# PMIC.net
KiCad netlist of a schematic drawn in Altium Designer
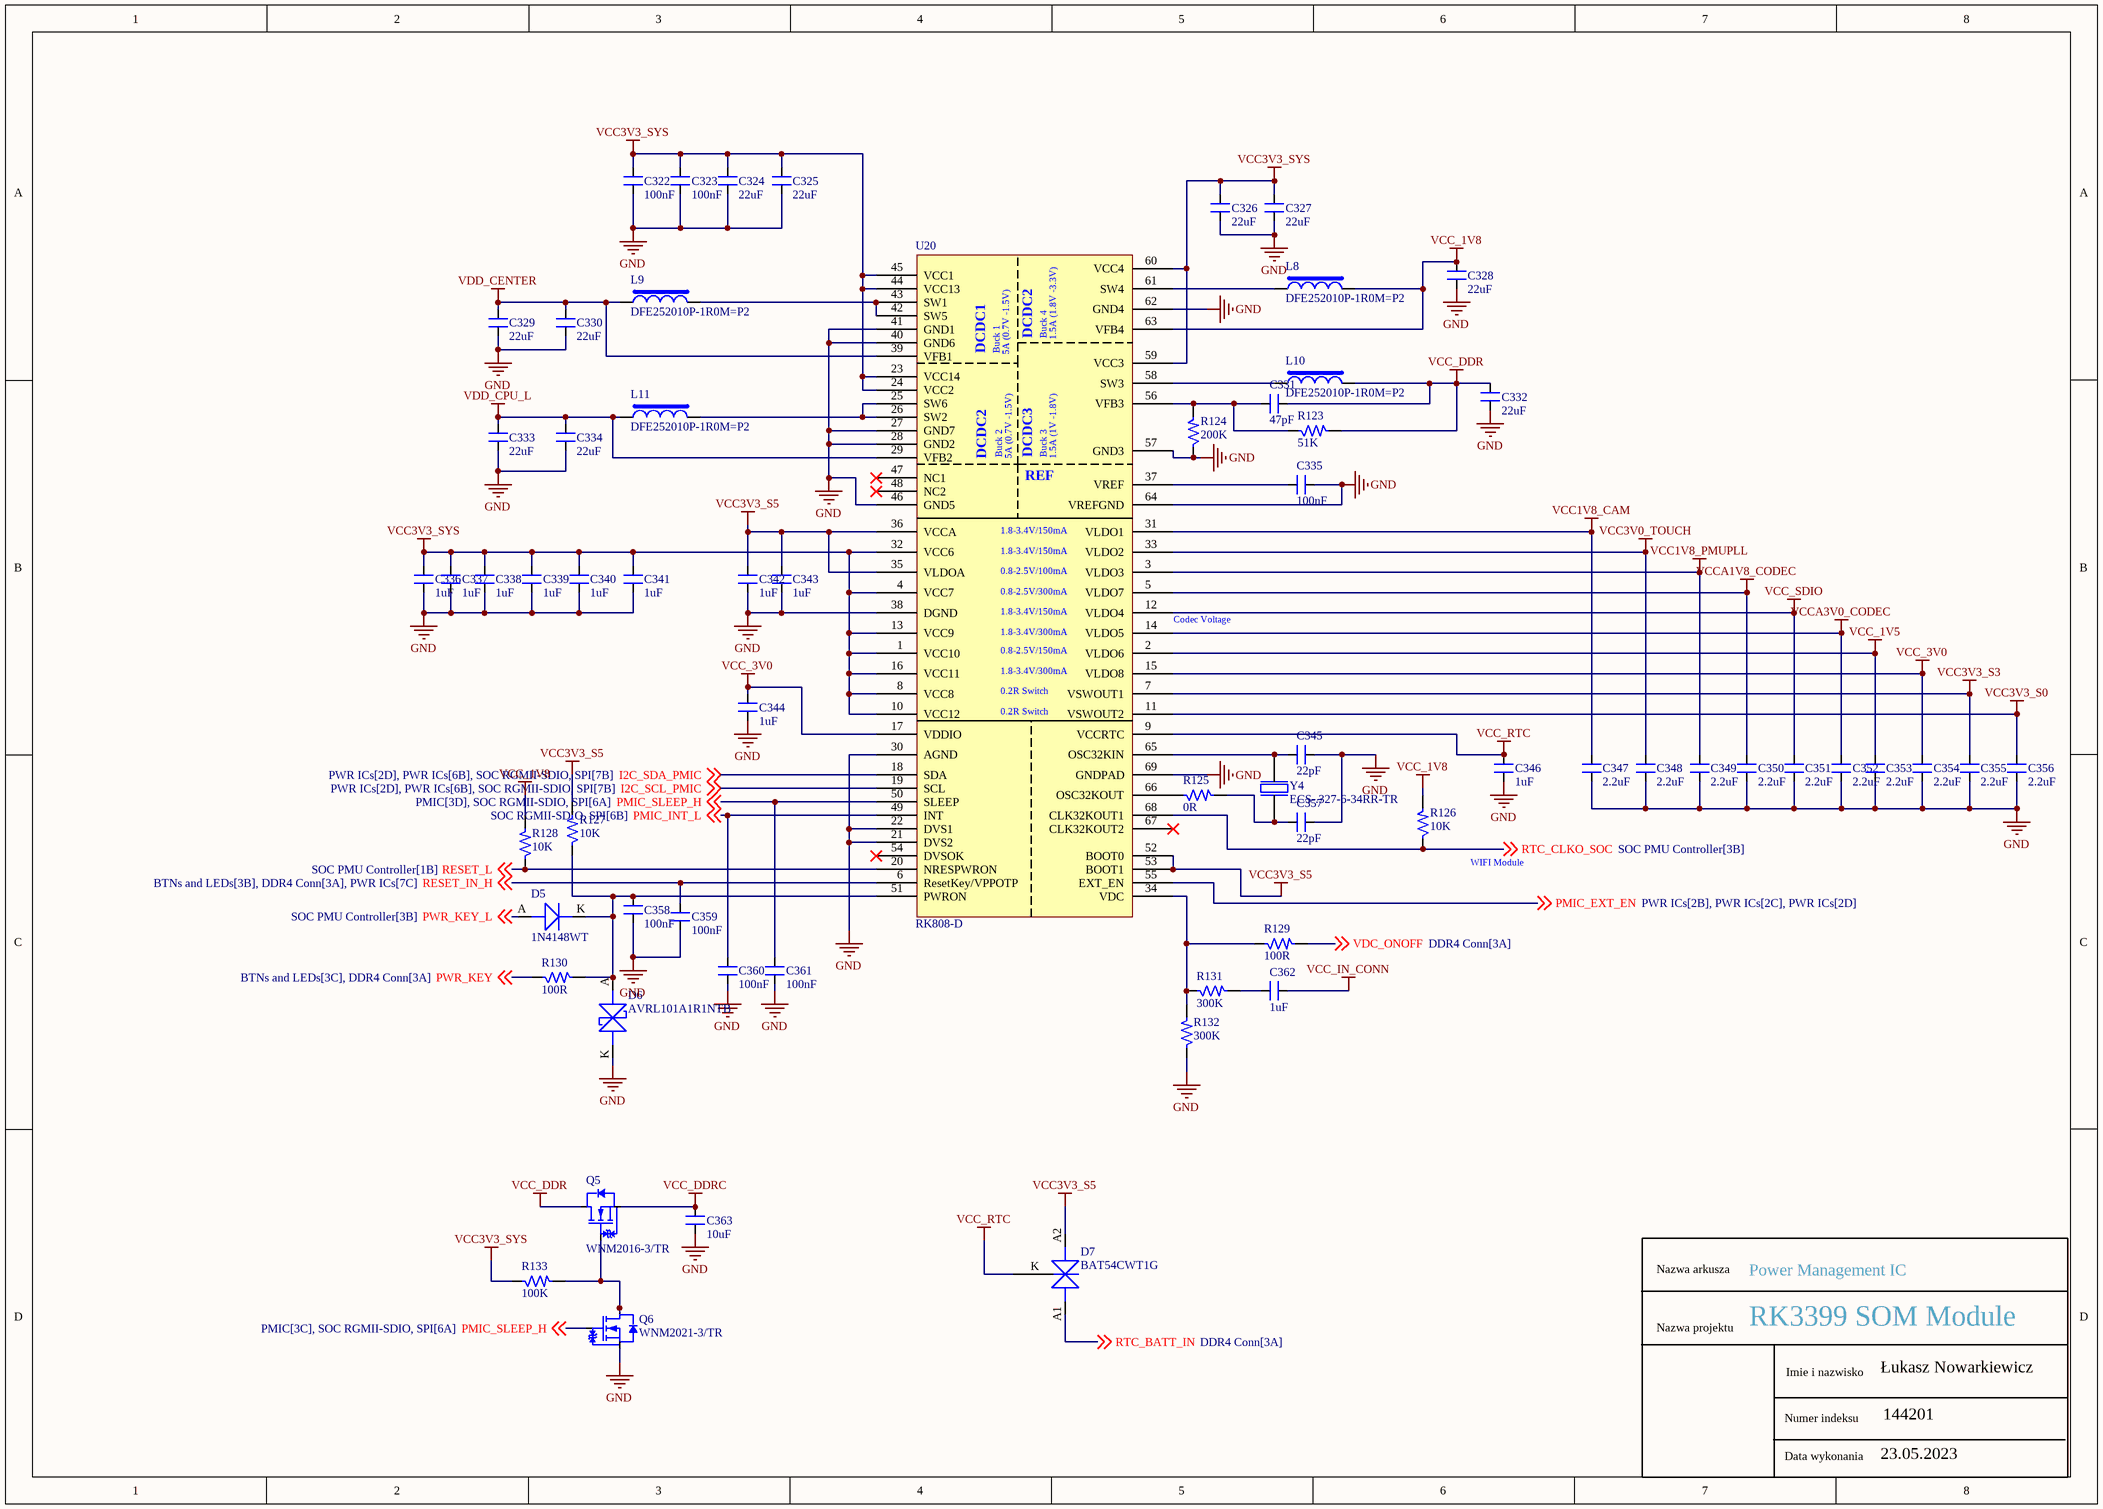
[diagram p0: PMIC.SchDoc]

(export (version "E")
  (design (tool "Eeschema 10.0.6"))
  (components
    (comp (ref "C322")
      (value "100nF")
      (footprint "CAP_0402")
      (description "0.1µF ±10% 25V Ceramic Capacitor X7R 0402 (1005 Metric)")
      (fields
        (field (name "MANUFACTURER") "Walsin Technology Corporation")
        (field (name "MANUFACTURER PART NUMBER") "0402B104K250CT")
      )
      (libsource (lib "RK3399 _Module_Schlib") (part "CAP_100nF-25V-10%-0402"))
    )
    (comp (ref "C323")
      (value "100nF")
      (footprint "CAP_0402")
      (description "0.1µF ±10% 25V Ceramic Capacitor X7R 0402 (1005 Metric)")
      (fields
        (field (name "MANUFACTURER") "Walsin Technology Corporation")
        (field (name "MANUFACTURER PART NUMBER") "0402B104K250CT")
      )
      (libsource (lib "RK3399 _Module_Schlib") (part "CAP_100nF-25V-10%-0402"))
    )
    (comp (ref "C324")
      (value "22uF")
      (footprint "CAP_0603")
      (description "22µF ±20% 10V Ceramic Capacitor X5R 0603 (1608 Metric)")
      (fields
        (field (name "MANUFACTURER") "Murata Electronics")
        (field (name "MANUFACTURER PART NUMBER") "GRM188R61A226ME15D")
      )
      (libsource (lib "RK3399 _Module_Schlib") (part "CAP_22uF-10V-20%-0603"))
    )
    (comp (ref "C325")
      (value "22uF")
      (footprint "CAP_0603")
      (description "22µF ±20% 10V Ceramic Capacitor X5R 0603 (1608 Metric)")
      (fields
        (field (name "MANUFACTURER") "Murata Electronics")
        (field (name "MANUFACTURER PART NUMBER") "GRM188R61A226ME15D")
      )
      (libsource (lib "RK3399 _Module_Schlib") (part "CAP_22uF-10V-20%-0603"))
    )
    (comp (ref "C326")
      (value "22uF")
      (footprint "CAP_0603")
      (description "22µF ±20% 10V Ceramic Capacitor X5R 0603 (1608 Metric)")
      (fields
        (field (name "MANUFACTURER") "Murata Electronics")
        (field (name "MANUFACTURER PART NUMBER") "GRM188R61A226ME15D")
      )
      (libsource (lib "RK3399 _Module_Schlib") (part "CAP_22uF-10V-20%-0603"))
    )
    (comp (ref "C327")
      (value "22uF")
      (footprint "CAP_0603")
      (description "22µF ±20% 10V Ceramic Capacitor X5R 0603 (1608 Metric)")
      (fields
        (field (name "MANUFACTURER") "Murata Electronics")
        (field (name "MANUFACTURER PART NUMBER") "GRM188R61A226ME15D")
      )
      (libsource (lib "RK3399 _Module_Schlib") (part "CAP_22uF-10V-20%-0603"))
    )
    (comp (ref "C328")
      (value "22uF")
      (footprint "CAP_0603")
      (description "22µF ±20% 10V Ceramic Capacitor X5R 0603 (1608 Metric)")
      (fields
        (field (name "MANUFACTURER") "Murata Electronics")
        (field (name "MANUFACTURER PART NUMBER") "GRM188R61A226ME15D")
      )
      (libsource (lib "RK3399 _Module_Schlib") (part "CAP_22uF-10V-20%-0603"))
    )
    (comp (ref "C329")
      (value "22uF")
      (footprint "CAP_0603")
      (description "22µF ±20% 10V Ceramic Capacitor X5R 0603 (1608 Metric)")
      (fields
        (field (name "MANUFACTURER") "Murata Electronics")
        (field (name "MANUFACTURER PART NUMBER") "GRM188R61A226ME15D")
      )
      (libsource (lib "RK3399 _Module_Schlib") (part "CAP_22uF-10V-20%-0603"))
    )
    (comp (ref "C330")
      (value "22uF")
      (footprint "CAP_0603")
      (description "22µF ±20% 10V Ceramic Capacitor X5R 0603 (1608 Metric)")
      (fields
        (field (name "MANUFACTURER") "Murata Electronics")
        (field (name "MANUFACTURER PART NUMBER") "GRM188R61A226ME15D")
      )
      (libsource (lib "RK3399 _Module_Schlib") (part "CAP_22uF-10V-20%-0603"))
    )
    (comp (ref "C331")
      (value "47pF")
      (footprint "CAP_0402")
      (description "47pF ±10% 10V Ceramic Capacitor C0G, NP0 0402 (1005 Metric)")
      (fields
        (field (name "MANUFACTURER") "KEMET")
        (field (name "MANUFACTURER PART NUMBER") "C0402C470K8GAC7867")
      )
      (libsource (lib "RK3399 _Module_Schlib") (part "CAP_47pF-10V-10%-0402"))
    )
    (comp (ref "C332")
      (value "22uF")
      (footprint "CAP_0603")
      (description "22µF ±20% 10V Ceramic Capacitor X5R 0603 (1608 Metric)")
      (fields
        (field (name "MANUFACTURER") "Murata Electronics")
        (field (name "MANUFACTURER PART NUMBER") "GRM188R61A226ME15D")
      )
      (libsource (lib "RK3399 _Module_Schlib") (part "CAP_22uF-10V-20%-0603"))
    )
    (comp (ref "C333")
      (value "22uF")
      (footprint "CAP_0603")
      (description "22µF ±20% 10V Ceramic Capacitor X5R 0603 (1608 Metric)")
      (fields
        (field (name "MANUFACTURER") "Murata Electronics")
        (field (name "MANUFACTURER PART NUMBER") "GRM188R61A226ME15D")
      )
      (libsource (lib "RK3399 _Module_Schlib") (part "CAP_22uF-10V-20%-0603"))
    )
    (comp (ref "C334")
      (value "22uF")
      (footprint "CAP_0603")
      (description "22µF ±20% 10V Ceramic Capacitor X5R 0603 (1608 Metric)")
      (fields
        (field (name "MANUFACTURER") "Murata Electronics")
        (field (name "MANUFACTURER PART NUMBER") "GRM188R61A226ME15D")
      )
      (libsource (lib "RK3399 _Module_Schlib") (part "CAP_22uF-10V-20%-0603"))
    )
    (comp (ref "C335")
      (value "100nF")
      (footprint "CAP_0402")
      (description "0.1µF ±10% 25V Ceramic Capacitor X7R 0402 (1005 Metric)")
      (fields
        (field (name "MANUFACTURER") "Walsin Technology Corporation")
        (field (name "MANUFACTURER PART NUMBER") "0402B104K250CT")
      )
      (libsource (lib "RK3399 _Module_Schlib") (part "CAP_100nF-25V-10%-0402"))
    )
    (comp (ref "C336")
      (value "1uF")
      (footprint "CAP_0402")
      (description "1µF ±10% 16V Ceramic Capacitor X5R 0402 (1005 Metric)")
      (fields
        (field (name "MANUFACTURER") "Knowles Novacap")
        (field (name "MANUFACTURER PART NUMBER") "0402BW105K160YT")
      )
      (libsource (lib "RK3399 _Module_Schlib") (part "CAP_1uF-16V-10%-0402"))
    )
    (comp (ref "C337")
      (value "1uF")
      (footprint "CAP_0402")
      (description "1µF ±10% 16V Ceramic Capacitor X5R 0402 (1005 Metric)")
      (fields
        (field (name "MANUFACTURER") "Knowles Novacap")
        (field (name "MANUFACTURER PART NUMBER") "0402BW105K160YT")
      )
      (libsource (lib "RK3399 _Module_Schlib") (part "CAP_1uF-16V-10%-0402"))
    )
    (comp (ref "C338")
      (value "1uF")
      (footprint "CAP_0402")
      (description "1µF ±10% 16V Ceramic Capacitor X5R 0402 (1005 Metric)")
      (fields
        (field (name "MANUFACTURER") "Knowles Novacap")
        (field (name "MANUFACTURER PART NUMBER") "0402BW105K160YT")
      )
      (libsource (lib "RK3399 _Module_Schlib") (part "CAP_1uF-16V-10%-0402"))
    )
    (comp (ref "C339")
      (value "1uF")
      (footprint "CAP_0402")
      (description "1µF ±10% 16V Ceramic Capacitor X5R 0402 (1005 Metric)")
      (fields
        (field (name "MANUFACTURER") "Knowles Novacap")
        (field (name "MANUFACTURER PART NUMBER") "0402BW105K160YT")
      )
      (libsource (lib "RK3399 _Module_Schlib") (part "CAP_1uF-16V-10%-0402"))
    )
    (comp (ref "C340")
      (value "1uF")
      (footprint "CAP_0402")
      (description "1µF ±10% 16V Ceramic Capacitor X5R 0402 (1005 Metric)")
      (fields
        (field (name "MANUFACTURER") "Knowles Novacap")
        (field (name "MANUFACTURER PART NUMBER") "0402BW105K160YT")
      )
      (libsource (lib "RK3399 _Module_Schlib") (part "CAP_1uF-16V-10%-0402"))
    )
    (comp (ref "C341")
      (value "1uF")
      (footprint "CAP_0402")
      (description "1µF ±10% 16V Ceramic Capacitor X5R 0402 (1005 Metric)")
      (fields
        (field (name "MANUFACTURER") "Knowles Novacap")
        (field (name "MANUFACTURER PART NUMBER") "0402BW105K160YT")
      )
      (libsource (lib "RK3399 _Module_Schlib") (part "CAP_1uF-16V-10%-0402"))
    )
    (comp (ref "C342")
      (value "1uF")
      (footprint "CAP_0402")
      (description "1µF ±10% 16V Ceramic Capacitor X5R 0402 (1005 Metric)")
      (fields
        (field (name "MANUFACTURER") "Knowles Novacap")
        (field (name "MANUFACTURER PART NUMBER") "0402BW105K160YT")
      )
      (libsource (lib "RK3399 _Module_Schlib") (part "CAP_1uF-16V-10%-0402"))
    )
    (comp (ref "C343")
      (value "1uF")
      (footprint "CAP_0402")
      (description "1µF ±10% 16V Ceramic Capacitor X5R 0402 (1005 Metric)")
      (fields
        (field (name "MANUFACTURER") "Knowles Novacap")
        (field (name "MANUFACTURER PART NUMBER") "0402BW105K160YT")
      )
      (libsource (lib "RK3399 _Module_Schlib") (part "CAP_1uF-16V-10%-0402"))
    )
    (comp (ref "C344")
      (value "1uF")
      (footprint "CAP_0402")
      (description "1µF ±10% 16V Ceramic Capacitor X5R 0402 (1005 Metric)")
      (fields
        (field (name "MANUFACTURER") "Knowles Novacap")
        (field (name "MANUFACTURER PART NUMBER") "0402BW105K160YT")
      )
      (libsource (lib "RK3399 _Module_Schlib") (part "CAP_1uF-16V-10%-0402"))
    )
    (comp (ref "C345")
      (value "22pF")
      (footprint "CAP_0402")
      (description "22pF ±10% 10V Ceramic Capacitor C0G, NP0 0402 (1005 Metric)")
      (fields
        (field (name "MANUFACTURER") "KEMET")
        (field (name "MANUFACTURER PART NUMBER") "C0402C220K8GACTU")
      )
      (libsource (lib "RK3399 _Module_Schlib") (part "CAP_22pF-10V-10%-0402"))
    )
    (comp (ref "C346")
      (value "1uF")
      (footprint "CAP_0402")
      (description "1µF ±10% 16V Ceramic Capacitor X5R 0402 (1005 Metric)")
      (fields
        (field (name "MANUFACTURER") "Knowles Novacap")
        (field (name "MANUFACTURER PART NUMBER") "0402BW105K160YT")
      )
      (libsource (lib "RK3399 _Module_Schlib") (part "CAP_1uF-16V-10%-0402"))
    )
    (comp (ref "C347")
      (value "2.2uF")
      (footprint "CAP_0402")
      (description "2.2µF ±10% 10V Ceramic Capacitor X5R 0402 (1005 Metric)")
      (fields
        (field (name "MANUFACTURER") "Murata Electronics")
        (field (name "MANUFACTURER PART NUMBER") "GRM155R61A225KE95D")
      )
      (libsource (lib "RK3399 _Module_Schlib") (part "CAP_2.2uF-10V-10%-0402"))
    )
    (comp (ref "C348")
      (value "2.2uF")
      (footprint "CAP_0402")
      (description "2.2µF ±10% 10V Ceramic Capacitor X5R 0402 (1005 Metric)")
      (fields
        (field (name "MANUFACTURER") "Murata Electronics")
        (field (name "MANUFACTURER PART NUMBER") "GRM155R61A225KE95D")
      )
      (libsource (lib "RK3399 _Module_Schlib") (part "CAP_2.2uF-10V-10%-0402"))
    )
    (comp (ref "C349")
      (value "2.2uF")
      (footprint "CAP_0402")
      (description "2.2µF ±10% 10V Ceramic Capacitor X5R 0402 (1005 Metric)")
      (fields
        (field (name "MANUFACTURER") "Murata Electronics")
        (field (name "MANUFACTURER PART NUMBER") "GRM155R61A225KE95D")
      )
      (libsource (lib "RK3399 _Module_Schlib") (part "CAP_2.2uF-10V-10%-0402"))
    )
    (comp (ref "C350")
      (value "2.2uF")
      (footprint "CAP_0402")
      (description "2.2µF ±10% 10V Ceramic Capacitor X5R 0402 (1005 Metric)")
      (fields
        (field (name "MANUFACTURER") "Murata Electronics")
        (field (name "MANUFACTURER PART NUMBER") "GRM155R61A225KE95D")
      )
      (libsource (lib "RK3399 _Module_Schlib") (part "CAP_2.2uF-10V-10%-0402"))
    )
    (comp (ref "C351")
      (value "2.2uF")
      (footprint "CAP_0402")
      (description "2.2µF ±10% 10V Ceramic Capacitor X5R 0402 (1005 Metric)")
      (fields
        (field (name "MANUFACTURER") "Murata Electronics")
        (field (name "MANUFACTURER PART NUMBER") "GRM155R61A225KE95D")
      )
      (libsource (lib "RK3399 _Module_Schlib") (part "CAP_2.2uF-10V-10%-0402"))
    )
    (comp (ref "C352")
      (value "2.2uF")
      (footprint "CAP_0402")
      (description "2.2µF ±10% 10V Ceramic Capacitor X5R 0402 (1005 Metric)")
      (fields
        (field (name "MANUFACTURER") "Murata Electronics")
        (field (name "MANUFACTURER PART NUMBER") "GRM155R61A225KE95D")
      )
      (libsource (lib "RK3399 _Module_Schlib") (part "CAP_2.2uF-10V-10%-0402"))
    )
    (comp (ref "C353")
      (value "2.2uF")
      (footprint "CAP_0402")
      (description "2.2µF ±10% 10V Ceramic Capacitor X5R 0402 (1005 Metric)")
      (fields
        (field (name "MANUFACTURER") "Murata Electronics")
        (field (name "MANUFACTURER PART NUMBER") "GRM155R61A225KE95D")
      )
      (libsource (lib "RK3399 _Module_Schlib") (part "CAP_2.2uF-10V-10%-0402"))
    )
    (comp (ref "C354")
      (value "2.2uF")
      (footprint "CAP_0402")
      (description "2.2µF ±10% 10V Ceramic Capacitor X5R 0402 (1005 Metric)")
      (fields
        (field (name "MANUFACTURER") "Murata Electronics")
        (field (name "MANUFACTURER PART NUMBER") "GRM155R61A225KE95D")
      )
      (libsource (lib "RK3399 _Module_Schlib") (part "CAP_2.2uF-10V-10%-0402"))
    )
    (comp (ref "C355")
      (value "2.2uF")
      (footprint "CAP_0402")
      (description "2.2µF ±10% 10V Ceramic Capacitor X5R 0402 (1005 Metric)")
      (fields
        (field (name "MANUFACTURER") "Murata Electronics")
        (field (name "MANUFACTURER PART NUMBER") "GRM155R61A225KE95D")
      )
      (libsource (lib "RK3399 _Module_Schlib") (part "CAP_2.2uF-10V-10%-0402"))
    )
    (comp (ref "C356")
      (value "2.2uF")
      (footprint "CAP_0402")
      (description "2.2µF ±10% 10V Ceramic Capacitor X5R 0402 (1005 Metric)")
      (fields
        (field (name "MANUFACTURER") "Murata Electronics")
        (field (name "MANUFACTURER PART NUMBER") "GRM155R61A225KE95D")
      )
      (libsource (lib "RK3399 _Module_Schlib") (part "CAP_2.2uF-10V-10%-0402"))
    )
    (comp (ref "C357")
      (value "22pF")
      (footprint "CAP_0402")
      (description "22pF ±10% 10V Ceramic Capacitor C0G, NP0 0402 (1005 Metric)")
      (fields
        (field (name "MANUFACTURER") "KEMET")
        (field (name "MANUFACTURER PART NUMBER") "C0402C220K8GACTU")
      )
      (libsource (lib "RK3399 _Module_Schlib") (part "CAP_22pF-10V-10%-0402"))
    )
    (comp (ref "C358")
      (value "100nF")
      (footprint "CAP_0402")
      (description "0.1µF ±10% 25V Ceramic Capacitor X7R 0402 (1005 Metric)")
      (fields
        (field (name "MANUFACTURER") "Walsin Technology Corporation")
        (field (name "MANUFACTURER PART NUMBER") "0402B104K250CT")
      )
      (libsource (lib "RK3399 _Module_Schlib") (part "CAP_100nF-25V-10%-0402"))
    )
    (comp (ref "C359")
      (value "100nF")
      (footprint "CAP_0402")
      (description "0.1µF ±10% 25V Ceramic Capacitor X7R 0402 (1005 Metric)")
      (fields
        (field (name "MANUFACTURER") "Walsin Technology Corporation")
        (field (name "MANUFACTURER PART NUMBER") "0402B104K250CT")
      )
      (libsource (lib "RK3399 _Module_Schlib") (part "CAP_100nF-25V-10%-0402"))
    )
    (comp (ref "C360")
      (value "100nF")
      (footprint "CAP_0402")
      (description "0.1µF ±10% 25V Ceramic Capacitor X7R 0402 (1005 Metric)")
      (fields
        (field (name "MANUFACTURER") "Walsin Technology Corporation")
        (field (name "MANUFACTURER PART NUMBER") "0402B104K250CT")
      )
      (libsource (lib "RK3399 _Module_Schlib") (part "CAP_100nF-25V-10%-0402"))
    )
    (comp (ref "C361")
      (value "100nF")
      (footprint "CAP_0402")
      (description "0.1µF ±10% 25V Ceramic Capacitor X7R 0402 (1005 Metric)")
      (fields
        (field (name "MANUFACTURER") "Walsin Technology Corporation")
        (field (name "MANUFACTURER PART NUMBER") "0402B104K250CT")
      )
      (libsource (lib "RK3399 _Module_Schlib") (part "CAP_100nF-25V-10%-0402"))
    )
    (comp (ref "C362")
      (value "1uF")
      (footprint "CAP_0402")
      (description "1µF ±10% 16V Ceramic Capacitor X5R 0402 (1005 Metric)")
      (fields
        (field (name "MANUFACTURER") "Knowles Novacap")
        (field (name "MANUFACTURER PART NUMBER") "0402BW105K160YT")
      )
      (libsource (lib "RK3399 _Module_Schlib") (part "CAP_1uF-16V-10%-0402"))
    )
    (comp (ref "C363")
      (value "10uF")
      (footprint "CAP_0402")
      (description "10µF ±20% 10V Ceramic Capacitor X5R 0402 (1005 Metric)")
      (fields
        (field (name "MANUFACTURER PART NUMBER") "CL05A106MP5NUNC")
        (field (name "MANUFACTURER") "Samsung Electro-Mechanics")
      )
      (libsource (lib "RK3399 _Module_Schlib") (part "CAP_10uF-10V-20%-0402"))
    )
    (comp (ref "D5")
      (value "1N4148WT")
      (footprint "DIO_SOD523")
      (description "Diode Standard 100V 300mA (DC) Surface Mount SOD-123")
      (fields (field (name "MANUFACTURER") "FAIRCHILD"))
      (libsource (lib "RK3399 _Module_Schlib") (part "DIO_75V-200mA-SOD-523F"))
    )
    (comp (ref "D6")
      (value "AVRL101A1R1NTB")
      (footprint "DIO_0402_SMD")
      (description "39V Varistor 1 Circuit Surface Mount, MLCV 0402 (1005 Metric)")
      (fields (field (name "MANUFACTURER") "TDK Corporation"))
      (libsource (lib "RK3399 _Module_Schlib") (part "DIO-T_10V-39V-0402"))
    )
    (comp (ref "D7")
      (value "BAT54CWT1G")
      (footprint "DIO_SOT-323-3")
      (description "Diode Array 1 Pair Common Cathode Schottky 30V 200mA (DC) Surface Mount SC-70, SOT-323")
      (fields (field (name "MANUFACTURER") "ON Semiconductor"))
      (libsource (lib "RK3399 _Module_Schlib") (part "DIO-S-A_30V-200mA-SOT-323"))
    )
    (comp (ref "L8")
      (value "DFE252010P-1R0M=P2")
      (footprint "IND_1008")
      (description "1µH Shielded Wirewound Inductor 3.8A 54mOhm Max 1008 (2520 Metric)")
      (fields (field (name "MANUFACTURER") "Murata Electronics"))
      (libsource (lib "RK3399 _Module_Schlib") (part "IND_1uH-3.8A-20%-1008"))
    )
    (comp (ref "L9")
      (value "DFE252010P-1R0M=P2")
      (footprint "IND_1008")
      (description "1µH Shielded Wirewound Inductor 3.8A 54mOhm Max 1008 (2520 Metric)")
      (fields (field (name "MANUFACTURER") "Murata Electronics"))
      (libsource (lib "RK3399 _Module_Schlib") (part "IND_1uH-3.8A-20%-1008"))
    )
    (comp (ref "L10")
      (value "DFE252010P-1R0M=P2")
      (footprint "IND_1008")
      (description "1µH Shielded Wirewound Inductor 3.8A 54mOhm Max 1008 (2520 Metric)")
      (fields (field (name "MANUFACTURER") "Murata Electronics"))
      (libsource (lib "RK3399 _Module_Schlib") (part "IND_1uH-3.8A-20%-1008"))
    )
    (comp (ref "L11")
      (value "DFE252010P-1R0M=P2")
      (footprint "IND_1008")
      (description "1µH Shielded Wirewound Inductor 3.8A 54mOhm Max 1008 (2520 Metric)")
      (fields (field (name "MANUFACTURER") "Murata Electronics"))
      (libsource (lib "RK3399 _Module_Schlib") (part "IND_1uH-3.8A-20%-1008"))
    )
    (comp (ref "Q5")
      (value "WNM2016-3/TR")
      (footprint "SOT 23-3")
      (description "N Channel 20V 2.9A 1V @ 250uA 47mΩ @ 3.6A,4.5V 700mW SOT-23(SOT-23-3) MOSFET RoHS")
      (fields (field (name "MANUFACTURER") "WILLSEMI(Will Semicon)"))
      (libsource (lib "RK3399 _Module_Schlib") (part "MOSFET-N_20V-2.9A-SOT-23"))
    )
    (comp (ref "Q6")
      (value "WNM2021-3/TR")
      (footprint "SOT-323-3")
      (description "N Channel 20V 820mA 850mV @ 250uA 310mΩ @ 550mA,4.5V 310mW SOT-323(SC-70) MOSFET RoHS")
      (fields (field (name "MANUFACTURER") "WILLSEMI(Will Semicon)"))
      (libsource (lib "RK3399 _Module_Schlib") (part "MOSFET-N_20V-820mA-SOT-323"))
    )
    (comp (ref "R123")
      (value "51K")
      (footprint "RES_0402")
      (description "51 kOhms ±1% 0.1W, 1/10W Chip Resistor 0402 (1005 Metric) Automotive AEC-Q200 Thick Film")
      (fields
        (field (name "MANUFACTURER") "Panasonic Electronic Components")
        (field (name "MANUFACTURER PART NUMBER") "ERJ-2RKF5102X")
      )
      (libsource (lib "RK3399 _Module_Schlib") (part "RES_51K-0.1W-1%-0402"))
    )
    (comp (ref "R124")
      (value "200K")
      (footprint "RES_0402")
      (description "200 kOhms ±1% 0.1W, 1/10W Chip Resistor 0402 (1005 Metric) Automotive AEC-Q200 Thick Film")
      (fields
        (field (name "MANUFACTURER") "Panasonic Electronic Components")
        (field (name "MANUFACTURER PART NUMBER") "ERJ-2RKF2003X")
      )
      (libsource (lib "RK3399 _Module_Schlib") (part "RES_200K-0.1W-1%-0402"))
    )
    (comp (ref "R125")
      (value "0R")
      (footprint "RES_0402")
      (description "0 Ohms Jumper 0.1W, 1/10W Chip Resistor 0402 (1005 Metric) Automotive AEC-Q200 Thick Film")
      (fields
        (field (name "MANUFACTURER") "Panasonic Electronic Components")
        (field (name "MANUFACTURER PART NUMBER") "ERJ-2GE0R00X")
      )
      (libsource (lib "RK3399 _Module_Schlib") (part "RES_0R-0.1W-1%-0402"))
    )
    (comp (ref "R126")
      (value "10K")
      (footprint "RES_0402")
      (description "10 kOhms ±1% 0.1W, 1/10W Chip Resistor 0402 (1005 Metric) Anti-Sulfur Thin Film")
      (fields
        (field (name "MANUFACTURER") "Vishay Beyschlag/Draloric/BC Components")
        (field (name "MANUFACTURER PART NUMBER") "MCS04020C1002FE000")
      )
      (libsource (lib "RK3399 _Module_Schlib") (part "RES_10K-0.1W-1%-0402"))
    )
    (comp (ref "R127")
      (value "10K")
      (footprint "RES_0402")
      (description "10 kOhms ±1% 0.1W, 1/10W Chip Resistor 0402 (1005 Metric) Anti-Sulfur Thin Film")
      (fields
        (field (name "MANUFACTURER") "Vishay Beyschlag/Draloric/BC Components")
        (field (name "MANUFACTURER PART NUMBER") "MCS04020C1002FE000")
      )
      (libsource (lib "RK3399 _Module_Schlib") (part "RES_10K-0.1W-1%-0402"))
    )
    (comp (ref "R128")
      (value "10K")
      (footprint "RES_0402")
      (description "10 kOhms ±1% 0.1W, 1/10W Chip Resistor 0402 (1005 Metric) Anti-Sulfur Thin Film")
      (fields
        (field (name "MANUFACTURER") "Vishay Beyschlag/Draloric/BC Components")
        (field (name "MANUFACTURER PART NUMBER") "MCS04020C1002FE000")
      )
      (libsource (lib "RK3399 _Module_Schlib") (part "RES_10K-0.1W-1%-0402"))
    )
    (comp (ref "R129")
      (value "100R")
      (footprint "RES_0402")
      (fields
        (field (name "MANUFACTURER") "KOA Speer Electronics, Inc.")
        (field (name "MANUFACTURER PART NUMBER") "RK73H1ETTP1000F")
      )
      (libsource (lib "RK3399 _Module_Schlib") (part "RES_100R-0.1W-1%-0402"))
    )
    (comp (ref "R130")
      (value "100R")
      (footprint "RES_0402")
      (fields
        (field (name "MANUFACTURER") "KOA Speer Electronics, Inc.")
        (field (name "MANUFACTURER PART NUMBER") "RK73H1ETTP1000F")
      )
      (libsource (lib "RK3399 _Module_Schlib") (part "RES_100R-0.1W-1%-0402"))
    )
    (comp (ref "R131")
      (value "300K")
      (footprint "RES_0402")
      (description "300 kOhms ±1% 0.1W, 1/10W Chip Resistor 0402 (1005 Metric) Automotive AEC-Q200 Thick Film")
      (fields
        (field (name "MANUFACTURER") "Panasonic Electronic Components")
        (field (name "MANUFACTURER PART NUMBER") "ERJ-2RKF3003X")
      )
      (libsource (lib "RK3399 _Module_Schlib") (part "RES_300K-0.1W-1%-0402"))
    )
    (comp (ref "R132")
      (value "300K")
      (footprint "RES_0402")
      (description "300 kOhms ±1% 0.1W, 1/10W Chip Resistor 0402 (1005 Metric) Automotive AEC-Q200 Thick Film")
      (fields
        (field (name "MANUFACTURER") "Panasonic Electronic Components")
        (field (name "MANUFACTURER PART NUMBER") "ERJ-2RKF3003X")
      )
      (libsource (lib "RK3399 _Module_Schlib") (part "RES_300K-0.1W-1%-0402"))
    )
    (comp (ref "R133")
      (value "100K")
      (footprint "RES_0402")
      (description "100 kOhms ±1% 0.1W, 1/10W Chip Resistor 0402 (1005 Metric) Anti-Sulfur Thin Film")
      (fields
        (field (name "MANUFACTURER") "Vishay Beyschlag/Draloric/BC Components")
        (field (name "MANUFACTURER PART NUMBER") "MCS04020C1003FE000")
      )
      (libsource (lib "RK3399 _Module_Schlib") (part "RES_100K-0.1W-1%-0402"))
    )
    (comp (ref "U20")
      (value "RK808-D")
      (footprint "QFN68_13.7_220.4X220.4_SMD")
      (description "The RK808 is a complete power supply solution for Portable systems.")
      (fields (field (name "MANUFACTURER") "Rockchip"))
      (libsource (lib "RK3399 _Module_Schlib") (part "IC_RK808-D-QFN68"))
    )
    (comp (ref "Y4")
      (value "ECS-.327-6-34RR-TR")
      (footprint "XTAL_ECS-.327-6-34RR-TR")
      (description "32.768kHz ±20ppm Crystal 12pF 80 kOhms 2-SMD, No Lead")
      (fields (field (name "MANUFACTURER") "Ecliptek"))
      (libsource (lib "RK3399 _Module_Schlib") (part "XTAL_32.768Khz-22pF-SMD"))
    )
  )
  (nets
    (net (code "1") (name "GND") (class "Default")
      (node (ref "C322") (pin "1") (pinfunction "1_1") (pintype "passive"))
      (node (ref "C323") (pin "1") (pinfunction "1_1") (pintype "passive"))
      (node (ref "C324") (pin "1") (pinfunction "1_1") (pintype "passive"))
      (node (ref "C325") (pin "1") (pinfunction "1_1") (pintype "passive"))
      (node (ref "C326") (pin "1") (pinfunction "1_1") (pintype "passive"))
      (node (ref "C327") (pin "1") (pinfunction "1_1") (pintype "passive"))
      (node (ref "C328") (pin "1") (pinfunction "1_1") (pintype "passive"))
      (node (ref "C329") (pin "1") (pinfunction "1_1") (pintype "passive"))
      (node (ref "C330") (pin "1") (pinfunction "1_1") (pintype "passive"))
      (node (ref "C332") (pin "1") (pinfunction "1_1") (pintype "passive"))
      (node (ref "C333") (pin "1") (pinfunction "1_1") (pintype "passive"))
      (node (ref "C334") (pin "1") (pinfunction "1_1") (pintype "passive"))
      (node (ref "C335") (pin "1") (pinfunction "1_1") (pintype "passive"))
      (node (ref "C336") (pin "2") (pinfunction "2_2") (pintype "passive"))
      (node (ref "C337") (pin "1") (pinfunction "1_1") (pintype "passive"))
      (node (ref "C338") (pin "1") (pinfunction "1_1") (pintype "passive"))
      (node (ref "C339") (pin "1") (pinfunction "1_1") (pintype "passive"))
      (node (ref "C340") (pin "1") (pinfunction "1_1") (pintype "passive"))
      (node (ref "C341") (pin "1") (pinfunction "1_1") (pintype "passive"))
      (node (ref "C342") (pin "1") (pinfunction "1_1") (pintype "passive"))
      (node (ref "C343") (pin "1") (pinfunction "1_1") (pintype "passive"))
      (node (ref "C344") (pin "1") (pinfunction "1_1") (pintype "passive"))
      (node (ref "C345") (pin "2") (pinfunction "2_2") (pintype "passive"))
      (node (ref "C346") (pin "1") (pinfunction "1_1") (pintype "passive"))
      (node (ref "C347") (pin "1") (pinfunction "1_1") (pintype "passive"))
      (node (ref "C348") (pin "1") (pinfunction "1_1") (pintype "passive"))
      (node (ref "C349") (pin "1") (pinfunction "1_1") (pintype "passive"))
      (node (ref "C350") (pin "1") (pinfunction "1_1") (pintype "passive"))
      (node (ref "C351") (pin "1") (pinfunction "1_1") (pintype "passive"))
      (node (ref "C352") (pin "1") (pinfunction "1_1") (pintype "passive"))
      (node (ref "C353") (pin "1") (pinfunction "1_1") (pintype "passive"))
      (node (ref "C354") (pin "1") (pinfunction "1_1") (pintype "passive"))
      (node (ref "C355") (pin "1") (pinfunction "1_1") (pintype "passive"))
      (node (ref "C356") (pin "1") (pinfunction "1_1") (pintype "passive"))
      (node (ref "C357") (pin "2") (pinfunction "2_2") (pintype "passive"))
      (node (ref "C358") (pin "1") (pinfunction "1_1") (pintype "passive"))
      (node (ref "C359") (pin "1") (pinfunction "1_1") (pintype "passive"))
      (node (ref "C360") (pin "1") (pinfunction "1_1") (pintype "passive"))
      (node (ref "C361") (pin "1") (pinfunction "1_1") (pintype "passive"))
      (node (ref "C363") (pin "1") (pinfunction "1_1") (pintype "passive"))
      (node (ref "D6") (pin "K") (pinfunction "K_K") (pintype "passive"))
      (node (ref "Q6") (pin "2") (pinfunction "S_2") (pintype "passive"))
      (node (ref "R124") (pin "1") (pinfunction "1_1") (pintype "passive"))
      (node (ref "R132") (pin "1") (pinfunction "1_1") (pintype "passive"))
      (node (ref "U20") (pin "21") (pinfunction "DVS2_21") (pintype "passive"))
      (node (ref "U20") (pin "22") (pinfunction "DVS1_22") (pintype "passive"))
      (node (ref "U20") (pin "27") (pinfunction "GND7_27") (pintype "passive"))
      (node (ref "U20") (pin "28") (pinfunction "GND2_28") (pintype "passive"))
      (node (ref "U20") (pin "30") (pinfunction "AGND_30") (pintype "passive"))
      (node (ref "U20") (pin "38") (pinfunction "DGND_38") (pintype "passive"))
      (node (ref "U20") (pin "40") (pinfunction "GND6_40") (pintype "passive"))
      (node (ref "U20") (pin "41") (pinfunction "GND1_41") (pintype "passive"))
      (node (ref "U20") (pin "46") (pinfunction "GND5_46") (pintype "passive"))
      (node (ref "U20") (pin "57") (pinfunction "GND3_57") (pintype "passive"))
      (node (ref "U20") (pin "62") (pinfunction "GND4_62") (pintype "passive"))
      (node (ref "U20") (pin "64") (pinfunction "VREFGND_64") (pintype "passive"))
      (node (ref "U20") (pin "69") (pinfunction "GNDPAD_69") (pintype "passive"))
    )
    (net (code "2") (name "I2C_SCL_PMIC") (class "Default")
      (node (ref "U20") (pin "19") (pinfunction "SCL_19") (pintype "passive"))
    )
    (net (code "3") (name "I2C_SDA_PMIC") (class "Default")
      (node (ref "U20") (pin "18") (pinfunction "SDA_18") (pintype "passive"))
    )
    (net (code "4") (name "Net-(C357-Pad1)") (class "Default")
      (node (ref "C357") (pin "1") (pinfunction "1_1") (pintype "passive"))
      (node (ref "R125") (pin "2") (pinfunction "2_2") (pintype "passive"))
      (node (ref "Y4") (pin "1") (pinfunction "1_1") (pintype "passive"))
    )
    (net (code "5") (name "Net-(C362-Pad2)") (class "Default")
      (node (ref "C362") (pin "2") (pinfunction "2_2") (pintype "passive"))
      (node (ref "R131") (pin "2") (pinfunction "2_2") (pintype "passive"))
    )
    (net (code "6") (name "Net-(D5-CATHODE)") (class "Default")
      (node (ref "C358") (pin "2") (pinfunction "2_2") (pintype "passive"))
      (node (ref "D5") (pin "K") (pinfunction "CATHODE_K") (pintype "passive"))
      (node (ref "D6") (pin "A") (pinfunction "A_A") (pintype "passive"))
      (node (ref "R127") (pin "1") (pinfunction "1_1") (pintype "passive"))
      (node (ref "R130") (pin "2") (pinfunction "2_2") (pintype "passive"))
      (node (ref "U20") (pin "51") (pinfunction "PWRON_51") (pintype "passive"))
    )
    (net (code "7") (name "Net-(Q5-G)") (class "Default")
      (node (ref "Q5") (pin "1") (pinfunction "G_1") (pintype "passive"))
      (node (ref "Q6") (pin "3") (pinfunction "D_3") (pintype "passive"))
      (node (ref "R133") (pin "2") (pinfunction "2_2") (pintype "passive"))
    )
    (net (code "8") (name "Net-(U20-OSC32KIN)") (class "Default")
      (node (ref "C345") (pin "1") (pinfunction "1_1") (pintype "passive"))
      (node (ref "U20") (pin "65") (pinfunction "OSC32KIN_65") (pintype "passive"))
      (node (ref "Y4") (pin "2") (pinfunction "2_2") (pintype "passive"))
    )
    (net (code "9") (name "Net-(U20-OSC32KOUT)") (class "Default")
      (node (ref "R125") (pin "1") (pinfunction "1_1") (pintype "passive"))
      (node (ref "U20") (pin "66") (pinfunction "OSC32KOUT_66") (pintype "passive"))
    )
    (net (code "10") (name "Net-(U20-SW1)") (class "Default")
      (node (ref "L9") (pin "2") (pinfunction "2_2") (pintype "passive"))
      (node (ref "U20") (pin "42") (pinfunction "SW5_42") (pintype "passive"))
      (node (ref "U20") (pin "43") (pinfunction "SW1_43") (pintype "passive"))
    )
    (net (code "11") (name "Net-(U20-SW2)") (class "Default")
      (node (ref "L11") (pin "2") (pinfunction "2_2") (pintype "passive"))
      (node (ref "U20") (pin "25") (pinfunction "SW6_25") (pintype "passive"))
      (node (ref "U20") (pin "26") (pinfunction "SW2_26") (pintype "passive"))
    )
    (net (code "12") (name "Net-(U20-SW3)") (class "Default")
      (node (ref "L10") (pin "1") (pinfunction "1_1") (pintype "passive"))
      (node (ref "U20") (pin "58") (pinfunction "SW3_58") (pintype "passive"))
    )
    (net (code "13") (name "Net-(U20-SW4)") (class "Default")
      (node (ref "L8") (pin "1") (pinfunction "1_1") (pintype "passive"))
      (node (ref "U20") (pin "61") (pinfunction "SW4_61") (pintype "passive"))
    )
    (net (code "14") (name "Net-(U20-VDC)") (class "Default")
      (node (ref "R129") (pin "1") (pinfunction "1_1") (pintype "passive"))
      (node (ref "R131") (pin "1") (pinfunction "1_1") (pintype "passive"))
      (node (ref "R132") (pin "2") (pinfunction "2_2") (pintype "passive"))
      (node (ref "U20") (pin "34") (pinfunction "VDC_34") (pintype "passive"))
    )
    (net (code "15") (name "Net-(U20-VFB3)") (class "Default")
      (node (ref "C331") (pin "1") (pinfunction "1_1") (pintype "passive"))
      (node (ref "R123") (pin "1") (pinfunction "1_1") (pintype "passive"))
      (node (ref "R124") (pin "2") (pinfunction "2_2") (pintype "passive"))
      (node (ref "U20") (pin "56") (pinfunction "VFB3_56") (pintype "passive"))
    )
    (net (code "16") (name "Net-(U20-VREF)") (class "Default")
      (node (ref "C335") (pin "2") (pinfunction "2_2") (pintype "passive"))
      (node (ref "U20") (pin "37") (pinfunction "VREF_37") (pintype "passive"))
    )
    (net (code "17") (name "PMIC_EXT_EN") (class "Default")
      (node (ref "U20") (pin "55") (pinfunction "EXT_EN_55") (pintype "passive"))
    )
    (net (code "18") (name "PMIC_INT_L") (class "Default")
      (node (ref "C360") (pin "2") (pinfunction "2_2") (pintype "passive"))
      (node (ref "U20") (pin "49") (pinfunction "INT_49") (pintype "passive"))
    )
    (net (code "19") (name "PMIC_SLEEP_H") (class "Default")
      (node (ref "C361") (pin "2") (pinfunction "2_2") (pintype "passive"))
      (node (ref "Q6") (pin "1") (pinfunction "G_1") (pintype "passive"))
      (node (ref "U20") (pin "50") (pinfunction "SLEEP_50") (pintype "passive"))
    )
    (net (code "20") (name "PWR_KEY") (class "Default")
      (node (ref "R130") (pin "1") (pinfunction "1_1") (pintype "passive"))
    )
    (net (code "21") (name "PWR_KEY_L") (class "Default")
      (node (ref "D5") (pin "A") (pinfunction "ANODE_A") (pintype "passive"))
    )
    (net (code "22") (name "RESET_IN_H") (class "Default")
      (node (ref "C359") (pin "2") (pinfunction "2_2") (pintype "passive"))
      (node (ref "U20") (pin "6") (pinfunction "ResetKey/VPPOTP_6") (pintype "passive"))
    )
    (net (code "23") (name "RESET_L") (class "Default")
      (node (ref "R128") (pin "1") (pinfunction "1_1") (pintype "passive"))
      (node (ref "U20") (pin "20") (pinfunction "NRESPWRON_20") (pintype "passive"))
    )
    (net (code "24") (name "RTC_BATT_IN") (class "Default")
      (node (ref "D7") (pin "A1") (pinfunction "A1_A1") (pintype "passive"))
    )
    (net (code "25") (name "RTC_CLKO_SOC") (class "Default")
      (node (ref "R126") (pin "1") (pinfunction "1_1") (pintype "passive"))
      (node (ref "U20") (pin "68") (pinfunction "CLK32KOUT1_68") (pintype "passive"))
    )
    (net (code "26") (name "VCC1V8_CAM") (class "Default")
      (node (ref "C347") (pin "2") (pinfunction "2_2") (pintype "passive"))
      (node (ref "U20") (pin "31") (pinfunction "VLDO1_31") (pintype "passive"))
    )
    (net (code "27") (name "VCC1V8_PMUPLL") (class "Default")
      (node (ref "C349") (pin "2") (pinfunction "2_2") (pintype "passive"))
      (node (ref "U20") (pin "3") (pinfunction "VLDO3_3") (pintype "passive"))
    )
    (net (code "28") (name "VCC3V0_TOUCH") (class "Default")
      (node (ref "C348") (pin "2") (pinfunction "2_2") (pintype "passive"))
      (node (ref "U20") (pin "33") (pinfunction "VLDO2_33") (pintype "passive"))
    )
    (net (code "29") (name "VCC3V3_S0") (class "Default")
      (node (ref "C356") (pin "2") (pinfunction "2_2") (pintype "passive"))
      (node (ref "U20") (pin "11") (pinfunction "VSWOUT2_11") (pintype "passive"))
    )
    (net (code "30") (name "VCC3V3_S3") (class "Default")
      (node (ref "C355") (pin "2") (pinfunction "2_2") (pintype "passive"))
      (node (ref "U20") (pin "7") (pinfunction "VSWOUT1_7") (pintype "passive"))
    )
    (net (code "31") (name "VCC3V3_S5") (class "Default")
      (node (ref "C342") (pin "2") (pinfunction "2_2") (pintype "passive"))
      (node (ref "C343") (pin "2") (pinfunction "2_2") (pintype "passive"))
      (node (ref "D7") (pin "A2") (pinfunction "A2_A2") (pintype "passive"))
      (node (ref "R127") (pin "2") (pinfunction "2_2") (pintype "passive"))
      (node (ref "U20") (pin "35") (pinfunction "VLDOA_35") (pintype "passive"))
      (node (ref "U20") (pin "36") (pinfunction "VCCA_36") (pintype "passive"))
      (node (ref "U20") (pin "52") (pinfunction "BOOT0_52") (pintype "passive"))
      (node (ref "U20") (pin "53") (pinfunction "BOOT1_53") (pintype "passive"))
    )
    (net (code "32") (name "VCC3V3_SYS") (class "Default")
      (node (ref "C322") (pin "2") (pinfunction "2_2") (pintype "passive"))
      (node (ref "C323") (pin "2") (pinfunction "2_2") (pintype "passive"))
      (node (ref "C324") (pin "2") (pinfunction "2_2") (pintype "passive"))
      (node (ref "C325") (pin "2") (pinfunction "2_2") (pintype "passive"))
      (node (ref "C326") (pin "2") (pinfunction "2_2") (pintype "passive"))
      (node (ref "C327") (pin "2") (pinfunction "2_2") (pintype "passive"))
      (node (ref "C336") (pin "1") (pinfunction "1_1") (pintype "passive"))
      (node (ref "C337") (pin "2") (pinfunction "2_2") (pintype "passive"))
      (node (ref "C338") (pin "2") (pinfunction "2_2") (pintype "passive"))
      (node (ref "C339") (pin "2") (pinfunction "2_2") (pintype "passive"))
      (node (ref "C340") (pin "2") (pinfunction "2_2") (pintype "passive"))
      (node (ref "C341") (pin "2") (pinfunction "2_2") (pintype "passive"))
      (node (ref "R133") (pin "1") (pinfunction "1_1") (pintype "passive"))
      (node (ref "U20") (pin "1") (pinfunction "VCC10_1") (pintype "passive"))
      (node (ref "U20") (pin "10") (pinfunction "VCC12_10") (pintype "passive"))
      (node (ref "U20") (pin "13") (pinfunction "VCC9_13") (pintype "passive"))
      (node (ref "U20") (pin "16") (pinfunction "VCC11_16") (pintype "passive"))
      (node (ref "U20") (pin "23") (pinfunction "VCC14_23") (pintype "passive"))
      (node (ref "U20") (pin "24") (pinfunction "VCC2_24") (pintype "passive"))
      (node (ref "U20") (pin "32") (pinfunction "VCC6_32") (pintype "passive"))
      (node (ref "U20") (pin "4") (pinfunction "VCC7_4") (pintype "passive"))
      (node (ref "U20") (pin "44") (pinfunction "VCC13_44") (pintype "passive"))
      (node (ref "U20") (pin "45") (pinfunction "VCC1_45") (pintype "passive"))
      (node (ref "U20") (pin "59") (pinfunction "VCC3_59") (pintype "passive"))
      (node (ref "U20") (pin "60") (pinfunction "VCC4_60") (pintype "passive"))
      (node (ref "U20") (pin "8") (pinfunction "VCC8_8") (pintype "passive"))
    )
    (net (code "33") (name "VCCA1V8_CODEC") (class "Default")
      (node (ref "C350") (pin "2") (pinfunction "2_2") (pintype "passive"))
      (node (ref "U20") (pin "5") (pinfunction "VLDO7_5") (pintype "passive"))
    )
    (net (code "34") (name "VCCA3V0_CODEC") (class "Default")
      (node (ref "C352") (pin "2") (pinfunction "2_2") (pintype "passive"))
      (node (ref "U20") (pin "14") (pinfunction "VLDO5_14") (pintype "passive"))
    )
    (net (code "35") (name "VCC_1V5") (class "Default")
      (node (ref "C353") (pin "2") (pinfunction "2_2") (pintype "passive"))
      (node (ref "U20") (pin "2") (pinfunction "VLDO6_2") (pintype "passive"))
    )
    (net (code "36") (name "VCC_1V8") (class "Default")
      (node (ref "C328") (pin "2") (pinfunction "2_2") (pintype "passive"))
      (node (ref "L8") (pin "2") (pinfunction "2_2") (pintype "passive"))
      (node (ref "R126") (pin "2") (pinfunction "2_2") (pintype "passive"))
      (node (ref "R128") (pin "2") (pinfunction "2_2") (pintype "passive"))
      (node (ref "U20") (pin "63") (pinfunction "VFB4_63") (pintype "passive"))
    )
    (net (code "37") (name "VCC_3V0") (class "Default")
      (node (ref "C344") (pin "2") (pinfunction "2_2") (pintype "passive"))
      (node (ref "C354") (pin "2") (pinfunction "2_2") (pintype "passive"))
      (node (ref "U20") (pin "15") (pinfunction "VLDO8_15") (pintype "passive"))
      (node (ref "U20") (pin "17") (pinfunction "VDDIO_17") (pintype "passive"))
    )
    (net (code "38") (name "VCC_DDR") (class "Default")
      (node (ref "C331") (pin "2") (pinfunction "2_2") (pintype "passive"))
      (node (ref "C332") (pin "2") (pinfunction "2_2") (pintype "passive"))
      (node (ref "L10") (pin "2") (pinfunction "2_2") (pintype "passive"))
      (node (ref "Q5") (pin "3") (pinfunction "D_3") (pintype "passive"))
      (node (ref "R123") (pin "2") (pinfunction "2_2") (pintype "passive"))
    )
    (net (code "39") (name "VCC_DDRC") (class "Default")
      (node (ref "C363") (pin "2") (pinfunction "2_2") (pintype "passive"))
      (node (ref "Q5") (pin "2") (pinfunction "S_2") (pintype "passive"))
    )
    (net (code "40") (name "VCC_IN_CONN") (class "Default")
      (node (ref "C362") (pin "1") (pinfunction "1_1") (pintype "passive"))
    )
    (net (code "41") (name "VCC_RTC") (class "Default")
      (node (ref "C346") (pin "2") (pinfunction "2_2") (pintype "passive"))
      (node (ref "D7") (pin "K") (pinfunction "K_K") (pintype "passive"))
      (node (ref "U20") (pin "9") (pinfunction "VCCRTC_9") (pintype "passive"))
    )
    (net (code "42") (name "VCC_SDIO") (class "Default")
      (node (ref "C351") (pin "2") (pinfunction "2_2") (pintype "passive"))
      (node (ref "U20") (pin "12") (pinfunction "VLDO4_12") (pintype "passive"))
    )
    (net (code "43") (name "VDC_ONOFF") (class "Default")
      (node (ref "R129") (pin "2") (pinfunction "2_2") (pintype "passive"))
    )
    (net (code "44") (name "VDD_CENTER") (class "Default")
      (node (ref "C329") (pin "2") (pinfunction "2_2") (pintype "passive"))
      (node (ref "C330") (pin "2") (pinfunction "2_2") (pintype "passive"))
      (node (ref "L9") (pin "1") (pinfunction "1_1") (pintype "passive"))
      (node (ref "U20") (pin "39") (pinfunction "VFB1_39") (pintype "passive"))
    )
    (net (code "45") (name "VDD_CPU_L") (class "Default")
      (node (ref "C333") (pin "2") (pinfunction "2_2") (pintype "passive"))
      (node (ref "C334") (pin "2") (pinfunction "2_2") (pintype "passive"))
      (node (ref "L11") (pin "1") (pinfunction "1_1") (pintype "passive"))
      (node (ref "U20") (pin "29") (pinfunction "VFB2_29") (pintype "passive"))
    )
    (net (code "46") (name "unconnected-(U20-CLK32KOUT2-Pad67)") (class "Default")
      (node (ref "U20") (pin "67") (pinfunction "CLK32KOUT2_67") (pintype "passive+no_connect"))
    )
    (net (code "47") (name "unconnected-(U20-DVSOK-Pad54)") (class "Default")
      (node (ref "U20") (pin "54") (pinfunction "DVSOK_54") (pintype "passive+no_connect"))
    )
    (net (code "48") (name "unconnected-(U20-NC1-Pad47)") (class "Default")
      (node (ref "U20") (pin "47") (pinfunction "NC1_47") (pintype "passive+no_connect"))
    )
    (net (code "49") (name "unconnected-(U20-NC2-Pad48)") (class "Default")
      (node (ref "U20") (pin "48") (pinfunction "NC2_48") (pintype "passive+no_connect"))
    )
  )
)
